# MINI_ESC_V1_0.net
KiCad netlist of a schematic drawn in Altium Designer
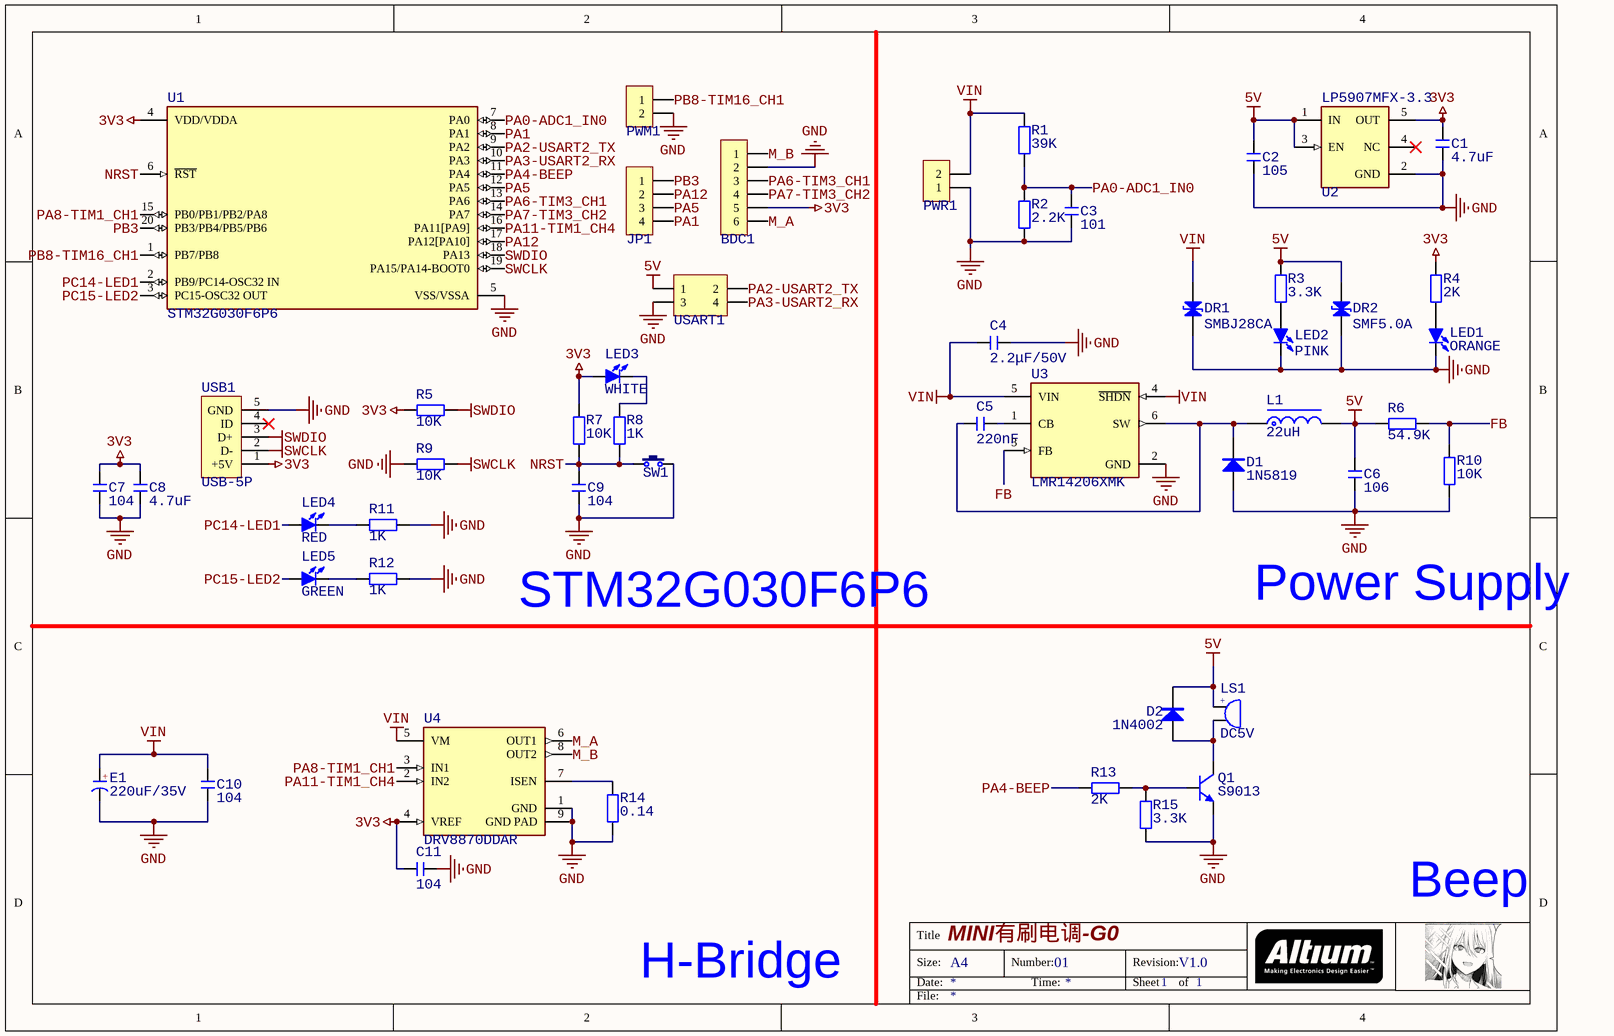
[diagram p0: MINI_ESC_V1.0.SchDoc]

(export (version "E")
  (design (tool "Eeschema 10.0.6"))
  (components
    (comp (ref "BDC1")
      (value "HDR-1X6")
      (footprint "XH2.54-LS-6P")
      (description "6P接插件")
      (libsource (lib "4.6   - 接插件-脚距2.54") (part "Header 6"))
    )
    (comp (ref "C1")
      (value "4.7uF")
      (footprint "C 0603_L")
      (description "无极性贴片电容")
      (libsource (lib "3.1   - 电阻-电容-电感") (part "C"))
    )
    (comp (ref "C2")
      (value "105")
      (footprint "C 0603_L")
      (description "无极性贴片电容")
      (libsource (lib "3.1   - 电阻-电容-电感") (part "C"))
    )
    (comp (ref "C3")
      (value "101")
      (footprint "C 0603_L")
      (description "无极性贴片电容")
      (libsource (lib "3.1   - 电阻-电容-电感") (part "C"))
    )
    (comp (ref "C4")
      (value "2.2μF/50V")
      (footprint "C 0603_L")
      (description "无极性贴片电容")
      (libsource (lib "3.1   - 电阻-电容-电感") (part "C"))
    )
    (comp (ref "C5")
      (value "220nF")
      (footprint "C 0603_L")
      (description "无极性贴片电容")
      (libsource (lib "3.1   - 电阻-电容-电感") (part "C"))
    )
    (comp (ref "C6")
      (value "106")
      (footprint "C 0603_L")
      (description "无极性贴片电容")
      (libsource (lib "3.1   - 电阻-电容-电感") (part "C"))
    )
    (comp (ref "C7")
      (value "104")
      (footprint "C 0402_L")
      (description "无极性贴片电容")
      (libsource (lib "3.1   - 电阻-电容-电感") (part "C"))
    )
    (comp (ref "C8")
      (value "4.7uF")
      (footprint "C 0402_L")
      (description "无极性贴片电容")
      (libsource (lib "3.1   - 电阻-电容-电感") (part "C"))
    )
    (comp (ref "C9")
      (value "104")
      (footprint "C 0603_L")
      (description "无极性贴片电容")
      (libsource (lib "3.1   - 电阻-电容-电感") (part "C"))
    )
    (comp (ref "C10")
      (value "104")
      (footprint "C 0402_L")
      (description "无极性贴片电容")
      (libsource (lib "3.1   - 电阻-电容-电感") (part "C"))
    )
    (comp (ref "C11")
      (value "104")
      (footprint "C 0402_L")
      (description "无极性贴片电容")
      (libsource (lib "3.1   - 电阻-电容-电感") (part "C"))
    )
    (comp (ref "D1")
      (value "1N5819")
      (footprint "SOD-123")
      (description "肖特基二极管")
      (libsource (lib "8.1   - 二极管-整流桥") (part "1N5819"))
    )
    (comp (ref "D2")
      (value "1N4002")
      (footprint "SOD-123")
      (description "整流二极管")
      (libsource (lib "8.1   - 二极管-整流桥") (part "1N4007"))
    )
    (comp (ref "DR1")
      (value "SMBJ28CA")
      (footprint "Diode:SMB")
      (description "瞬态电压抑制二极管")
      (libsource (lib "8.1   - 二极管-整流桥") (part "DR"))
    )
    (comp (ref "DR2")
      (value "SMF5.0A")
      (footprint "SOD-323")
      (description "瞬态电压抑制二极管")
      (libsource (lib "8.1   - 二极管-整流桥") (part "DR"))
    )
    (comp (ref "E1")
      (value "220uF/35V")
      (footprint "CAP 3.5*8*11.5-H - BK")
      (description "直插电解电容")
      (libsource (lib "3.1   - 电阻-电容-电感") (part "C-CAP"))
    )
    (comp (ref "JP1")
      (value "HDR-1X4")
      (footprint "HDR2.54-LI-4P")
      (description "4P接插件")
      (libsource (lib "4.6   - 接插件-脚距2.54") (part "Header 4"))
    )
    (comp (ref "L1")
      (value "22uH")
      (footprint "NR4030")
      (description "NR磁胶电感")
      (libsource (lib "3.1   - 电阻-电容-电感") (part "L-NR"))
    )
    (comp (ref "LED1")
      (value "ORANGE")
      (footprint "LED 0603R")
      (description "贴片LED")
      (libsource (lib "9.1   - LED") (part "LED-SMD"))
    )
    (comp (ref "LED2")
      (value "PINK")
      (footprint "LED 0603R")
      (description "贴片LED")
      (libsource (lib "9.1   - LED") (part "LED-SMD"))
    )
    (comp (ref "LED3")
      (value "WHITE")
      (footprint "LED 0603W")
      (description "贴片LED")
      (libsource (lib "9.1   - LED") (part "LED-SMD"))
    )
    (comp (ref "LED4")
      (value "RED")
      (footprint "LED 0603R")
      (description "贴片LED")
      (libsource (lib "9.1   - LED") (part "LED-SMD"))
    )
    (comp (ref "LED5")
      (value "GREEN")
      (footprint "LED 0603G")
      (description "贴片LED")
      (libsource (lib "9.1   - LED") (part "LED-SMD"))
    )
    (comp (ref "LS1")
      (value "DC5V")
      (footprint "BEEP 6.5x12x6")
      (description "蜂鸣器")
      (libsource (lib "15.1 - 未分类器件") (part "BEEP"))
    )
    (comp (ref "PWM1")
      (value "HDR-1X2")
      (footprint "GH1.25-LS-2P")
      (description "2P接插件")
      (libsource (lib "4.2   - 接插件-脚距1.25") (part "Header 2"))
    )
    (comp (ref "PWR1")
      (value "绿头卧式2P")
      (footprint "15EDGVM-02P-3.81mm")
      (description "3.81间距")
      (libsource (lib "Elmo接插件") (part "绿头卧式2P"))
    )
    (comp (ref "Q1")
      (value "S9013")
      (footprint "SOT23-3L")
      (description "低频放大-NPN型")
      (libsource (lib "6.2   - 三极管") (part "9013-SMD"))
    )
    (comp (ref "R1")
      (value "39K")
      (footprint "R 0603_L")
      (description "贴片电阻")
      (libsource (lib "3.1   - 电阻-电容-电感") (part "R"))
    )
    (comp (ref "R2")
      (value "2.2K")
      (footprint "R 0603_L")
      (description "贴片电阻")
      (libsource (lib "3.1   - 电阻-电容-电感") (part "R"))
    )
    (comp (ref "R3")
      (value "3.3K")
      (footprint "R 0603_L")
      (description "贴片电阻")
      (libsource (lib "3.1   - 电阻-电容-电感") (part "R"))
    )
    (comp (ref "R4")
      (value "2K")
      (footprint "R 0603_L")
      (description "贴片电阻")
      (libsource (lib "3.1   - 电阻-电容-电感") (part "R"))
    )
    (comp (ref "R5")
      (value "10K")
      (footprint "R 0603_L")
      (description "贴片电阻")
      (libsource (lib "3.1   - 电阻-电容-电感") (part "R"))
    )
    (comp (ref "R6")
      (value "54.9K")
      (footprint "R 0603_L")
      (description "贴片电阻")
      (libsource (lib "3.1   - 电阻-电容-电感") (part "R"))
    )
    (comp (ref "R7")
      (value "10K")
      (footprint "R 0603_L")
      (description "贴片电阻")
      (libsource (lib "3.1   - 电阻-电容-电感") (part "R"))
    )
    (comp (ref "R8")
      (value "1K")
      (footprint "R 0603_L")
      (description "贴片电阻")
      (libsource (lib "3.1   - 电阻-电容-电感") (part "R"))
    )
    (comp (ref "R9")
      (value "10K")
      (footprint "R 0603_L")
      (description "贴片电阻")
      (libsource (lib "3.1   - 电阻-电容-电感") (part "R"))
    )
    (comp (ref "R10")
      (value "10K")
      (footprint "R 0603_L")
      (description "贴片电阻")
      (libsource (lib "3.1   - 电阻-电容-电感") (part "R"))
    )
    (comp (ref "R11")
      (value "1K")
      (footprint "R 0402_L")
      (description "贴片电阻")
      (libsource (lib "3.1   - 电阻-电容-电感") (part "R"))
    )
    (comp (ref "R12")
      (value "1K")
      (footprint "R 0402_L")
      (description "贴片电阻")
      (libsource (lib "3.1   - 电阻-电容-电感") (part "R"))
    )
    (comp (ref "R13")
      (value "2K")
      (footprint "R 0603_L")
      (description "贴片电阻")
      (libsource (lib "3.1   - 电阻-电容-电感") (part "R"))
    )
    (comp (ref "R14")
      (value "0.14")
      (footprint "R 1206_L")
      (description "贴片电阻")
      (libsource (lib "3.1   - 电阻-电容-电感") (part "R"))
    )
    (comp (ref "R15")
      (value "3.3K")
      (footprint "R 0603_L")
      (description "贴片电阻")
      (libsource (lib "3.1   - 电阻-电容-电感") (part "R"))
    )
    (comp (ref "SW1")
      (value "6x6x5")
      (footprint "TS 2PIN 6x6x4.8")
      (description "2脚贴片6x6无声硅胶轻触开关")
      (libsource (lib "KEY") (part "TSW SMD-2Pin-6x6"))
    )
    (comp (ref "U1")
      (value "STM32G030F6P6")
      (footprint "STMicroelectronics_TSSOP20-YA_IPC_C")
      (libsource (lib "高级IC") (part "STM32G030F6P6"))
    )
    (comp (ref "U2")
      (value "LP5907MFX-3.3")
      (footprint "Diodes_SOT25_MFG")
      (description "250-mA ultra-low-noise low-IQ low-dropout (LDO) linear regulator 5-SOT-23 -40 to 125")
      (libsource (lib "高级IC") (part "LP5907MFX-3.3-NOPB"))
    )
    (comp (ref "U3")
      (value "LMR14206XMK")
      (footprint "Texas_Instruments_DDC0006A_0")
      (description "4.5V to 42V, 0.6A Step-Down DC/DC Switching Regulator in SOT-23 Package 6-SOT-23-THIN -40 to 125")
      (libsource (lib "高级IC") (part "LMR14206XMK"))
    )
    (comp (ref "U4")
      (value "DRV8870DDAR")
      (footprint "Texas_Instruments_DDA0008J_IPC_C")
      (description "50-V, 3.6-A H-bridge motor driver with current regulation 8-SO PowerPAD -40 to 125")
      (libsource (lib "高级IC") (part "DRV8870DDAR"))
    )
    (comp (ref "USART1")
      (value "Header2X2")
      (footprint "HDR2.54-M-LS-2x2P")
      (description "2*2P接插件")
      (libsource (lib "4.6   - 接插件-脚距2.54") (part "Header 2X2"))
    )
    (comp (ref "USB1")
      (value "USB-5P")
      (footprint "USB-MICRO_E")
      (description "微型USB母座")
      (libsource (lib "4.1   - 接口类") (part "USB-5P"))
    )
  )
  (nets
    (net (code "1") (name "/FB") (class "Default")
      (node (ref "R10") (pin "1") (pinfunction "1_1") (pintype "passive"))
      (node (ref "R6") (pin "2") (pinfunction "2_2") (pintype "passive"))
      (node (ref "U3") (pin "3") (pinfunction "FB_3") (pintype "input"))
    )
    (net (code "2") (name "/M_A") (class "Default")
      (node (ref "BDC1") (pin "6") (pinfunction "6_6") (pintype "passive"))
      (node (ref "U4") (pin "6") (pinfunction "OUT1_6") (pintype "output"))
    )
    (net (code "3") (name "/M_B") (class "Default")
      (node (ref "BDC1") (pin "1") (pinfunction "1_1") (pintype "passive"))
      (node (ref "U4") (pin "8") (pinfunction "OUT2_8") (pintype "output"))
    )
    (net (code "4") (name "/NRST") (class "Default")
      (node (ref "C9") (pin "2") (pinfunction "2_2") (pintype "passive"))
      (node (ref "R7") (pin "1") (pinfunction "1_1") (pintype "passive"))
      (node (ref "R8") (pin "1") (pinfunction "1_1") (pintype "passive"))
      (node (ref "SW1") (pin "1") (pinfunction "1_1") (pintype "passive"))
      (node (ref "U1") (pin "6") (pinfunction "~{RST}_6") (pintype "input"))
    )
    (net (code "5") (name "/PA0-ADC1_IN0") (class "Default")
      (node (ref "C3") (pin "2") (pinfunction "2_2") (pintype "passive"))
      (node (ref "R1") (pin "1") (pinfunction "1_1") (pintype "passive"))
      (node (ref "R2") (pin "2") (pinfunction "2_2") (pintype "passive"))
      (node (ref "U1") (pin "7") (pinfunction "PA0_7") (pintype "bidirectional"))
    )
    (net (code "6") (name "/PA1") (class "Default")
      (node (ref "JP1") (pin "4") (pinfunction "4_4") (pintype "passive"))
      (node (ref "U1") (pin "8") (pinfunction "PA1_8") (pintype "bidirectional"))
    )
    (net (code "7") (name "/PA2-USART2_TX") (class "Default")
      (node (ref "U1") (pin "9") (pinfunction "PA2_9") (pintype "bidirectional"))
      (node (ref "USART1") (pin "2") (pinfunction "2_2") (pintype "passive"))
    )
    (net (code "8") (name "/PA3-USART2_RX") (class "Default")
      (node (ref "U1") (pin "10") (pinfunction "PA3_10") (pintype "bidirectional"))
      (node (ref "USART1") (pin "4") (pinfunction "4_4") (pintype "passive"))
    )
    (net (code "9") (name "/PA4-BEEP") (class "Default")
      (node (ref "R13") (pin "1") (pinfunction "1_1") (pintype "passive"))
      (node (ref "U1") (pin "11") (pinfunction "PA4_11") (pintype "bidirectional"))
    )
    (net (code "10") (name "/PA5") (class "Default")
      (node (ref "JP1") (pin "3") (pinfunction "3_3") (pintype "passive"))
      (node (ref "U1") (pin "12") (pinfunction "PA5_12") (pintype "bidirectional"))
    )
    (net (code "11") (name "/PA6-TIM3_CH1") (class "Default")
      (node (ref "BDC1") (pin "3") (pinfunction "3_3") (pintype "passive"))
      (node (ref "U1") (pin "13") (pinfunction "PA6_13") (pintype "bidirectional"))
    )
    (net (code "12") (name "/PA7-TIM3_CH2") (class "Default")
      (node (ref "BDC1") (pin "4") (pinfunction "4_4") (pintype "passive"))
      (node (ref "U1") (pin "14") (pinfunction "PA7_14") (pintype "bidirectional"))
    )
    (net (code "13") (name "/PA8-TIM1_CH1") (class "Default")
      (node (ref "U1") (pin "15") (pinfunction "PB0/PB1/PB2/PA8_15") (pintype "bidirectional"))
      (node (ref "U4") (pin "3") (pinfunction "IN1_3") (pintype "input"))
    )
    (net (code "14") (name "/PA11-TIM1_CH4") (class "Default")
      (node (ref "U1") (pin "16") (pinfunction "PA11[PA9]_16") (pintype "bidirectional"))
      (node (ref "U4") (pin "2") (pinfunction "IN2_2") (pintype "input"))
    )
    (net (code "15") (name "/PA12") (class "Default")
      (node (ref "JP1") (pin "2") (pinfunction "2_2") (pintype "passive"))
      (node (ref "U1") (pin "17") (pinfunction "PA12[PA10]_17") (pintype "bidirectional"))
    )
    (net (code "16") (name "/PB3") (class "Default")
      (node (ref "JP1") (pin "1") (pinfunction "1_1") (pintype "passive"))
      (node (ref "U1") (pin "20") (pinfunction "PB3/PB4/PB5/PB6_20") (pintype "bidirectional"))
    )
    (net (code "17") (name "/PB8-TIM16_CH1") (class "Default")
      (node (ref "PWM1") (pin "1") (pinfunction "1_1") (pintype "passive"))
      (node (ref "U1") (pin "1") (pinfunction "PB7/PB8_1") (pintype "bidirectional"))
    )
    (net (code "18") (name "/PC14-LED1") (class "Default")
      (node (ref "LED4") (pin "1") (pinfunction "A_1") (pintype "passive"))
      (node (ref "U1") (pin "2") (pinfunction "PB9/PC14-OSC32_IN_2") (pintype "bidirectional"))
    )
    (net (code "19") (name "/PC15-LED2") (class "Default")
      (node (ref "LED5") (pin "1") (pinfunction "A_1") (pintype "passive"))
      (node (ref "U1") (pin "3") (pinfunction "PC15-OSC32_OUT_3") (pintype "bidirectional"))
    )
    (net (code "20") (name "3V3") (class "Default")
      (node (ref "BDC1") (pin "5") (pinfunction "5_5") (pintype "passive"))
      (node (ref "C1") (pin "2") (pinfunction "2_2") (pintype "passive"))
      (node (ref "C11") (pin "2") (pinfunction "2_2") (pintype "passive"))
      (node (ref "C7") (pin "2") (pinfunction "2_2") (pintype "passive"))
      (node (ref "C8") (pin "2") (pinfunction "2_2") (pintype "passive"))
      (node (ref "LED3") (pin "1") (pinfunction "A_1") (pintype "passive"))
      (node (ref "R4") (pin "2") (pinfunction "2_2") (pintype "passive"))
      (node (ref "R5") (pin "2") (pinfunction "2_2") (pintype "passive"))
      (node (ref "R7") (pin "2") (pinfunction "2_2") (pintype "passive"))
      (node (ref "U1") (pin "4") (pinfunction "VDD/VDDA_4") (pintype "power_in"))
      (node (ref "U2") (pin "5") (pinfunction "OUT_5") (pintype "power_in"))
      (node (ref "U4") (pin "4") (pinfunction "VREF_4") (pintype "input"))
      (node (ref "USB1") (pin "1") (pinfunction "+5V_1") (pintype "passive"))
    )
    (net (code "21") (name "5V") (class "Default")
      (node (ref "C2") (pin "2") (pinfunction "2_2") (pintype "passive"))
      (node (ref "C6") (pin "1") (pinfunction "1_1") (pintype "passive"))
      (node (ref "D2") (pin "2") (pinfunction "K_2") (pintype "passive"))
      (node (ref "DR2") (pin "2") (pinfunction "K_2") (pintype "passive"))
      (node (ref "L1") (pin "2") (pinfunction "2_2") (pintype "passive"))
      (node (ref "LS1") (pin "1") (pinfunction "1_1") (pintype "passive"))
      (node (ref "R3") (pin "2") (pinfunction "2_2") (pintype "passive"))
      (node (ref "R6") (pin "1") (pinfunction "1_1") (pintype "passive"))
      (node (ref "U2") (pin "1") (pinfunction "IN_1") (pintype "power_in"))
      (node (ref "U2") (pin "3") (pinfunction "EN_3") (pintype "input"))
      (node (ref "USART1") (pin "1") (pinfunction "1_1") (pintype "passive"))
    )
    (net (code "22") (name "GND") (class "Default")
      (node (ref "BDC1") (pin "2") (pinfunction "2_2") (pintype "passive"))
      (node (ref "C1") (pin "1") (pinfunction "1_1") (pintype "passive"))
      (node (ref "C10") (pin "1") (pinfunction "1_1") (pintype "passive"))
      (node (ref "C11") (pin "1") (pinfunction "1_1") (pintype "passive"))
      (node (ref "C2") (pin "1") (pinfunction "1_1") (pintype "passive"))
      (node (ref "C3") (pin "1") (pinfunction "1_1") (pintype "passive"))
      (node (ref "C4") (pin "2") (pinfunction "2_2") (pintype "passive"))
      (node (ref "C6") (pin "2") (pinfunction "2_2") (pintype "passive"))
      (node (ref "C7") (pin "1") (pinfunction "1_1") (pintype "passive"))
      (node (ref "C8") (pin "1") (pinfunction "1_1") (pintype "passive"))
      (node (ref "C9") (pin "1") (pinfunction "1_1") (pintype "passive"))
      (node (ref "D1") (pin "1") (pinfunction "A_1") (pintype "passive"))
      (node (ref "DR1") (pin "2") (pinfunction "K_2") (pintype "passive"))
      (node (ref "DR2") (pin "1") (pinfunction "A_1") (pintype "passive"))
      (node (ref "E1") (pin "2") (pinfunction "K_2") (pintype "passive"))
      (node (ref "LED1") (pin "2") (pinfunction "K_2") (pintype "passive"))
      (node (ref "LED2") (pin "2") (pinfunction "K_2") (pintype "passive"))
      (node (ref "PWM1") (pin "2") (pinfunction "2_2") (pintype "passive"))
      (node (ref "PWR1") (pin "1") (pinfunction "1_1") (pintype "passive"))
      (node (ref "Q1") (pin "2") (pinfunction "E_2") (pintype "passive"))
      (node (ref "R10") (pin "2") (pinfunction "2_2") (pintype "passive"))
      (node (ref "R11") (pin "1") (pinfunction "1_1") (pintype "passive"))
      (node (ref "R12") (pin "1") (pinfunction "1_1") (pintype "passive"))
      (node (ref "R14") (pin "1") (pinfunction "1_1") (pintype "passive"))
      (node (ref "R15") (pin "1") (pinfunction "1_1") (pintype "passive"))
      (node (ref "R2") (pin "1") (pinfunction "1_1") (pintype "passive"))
      (node (ref "R9") (pin "2") (pinfunction "2_2") (pintype "passive"))
      (node (ref "SW1") (pin "2") (pinfunction "2_2") (pintype "passive"))
      (node (ref "U1") (pin "5") (pinfunction "VSS/VSSA_5") (pintype "power_in"))
      (node (ref "U2") (pin "2") (pinfunction "GND_2") (pintype "power_in"))
      (node (ref "U3") (pin "2") (pinfunction "GND_2") (pintype "power_in"))
      (node (ref "U4") (pin "1") (pinfunction "GND_1") (pintype "power_in"))
      (node (ref "U4") (pin "9") (pinfunction "GND_PAD_9") (pintype "power_in"))
      (node (ref "USART1") (pin "3") (pinfunction "3_3") (pintype "passive"))
      (node (ref "USB1") (pin "5") (pinfunction "GND_5") (pintype "passive"))
    )
    (net (code "23") (name "Net-(D1-K)") (class "Default")
      (node (ref "C5") (pin "2") (pinfunction "2_2") (pintype "passive"))
      (node (ref "D1") (pin "2") (pinfunction "K_2") (pintype "passive"))
      (node (ref "L1") (pin "1") (pinfunction "1_1") (pintype "passive"))
      (node (ref "U3") (pin "6") (pinfunction "SW_6") (pintype "output"))
    )
    (net (code "24") (name "Net-(D2-A)") (class "Default")
      (node (ref "D2") (pin "1") (pinfunction "A_1") (pintype "passive"))
      (node (ref "LS1") (pin "2") (pinfunction "2_2") (pintype "passive"))
      (node (ref "Q1") (pin "3") (pinfunction "C_3") (pintype "passive"))
    )
    (net (code "25") (name "Net-(LED1-A)") (class "Default")
      (node (ref "LED1") (pin "1") (pinfunction "A_1") (pintype "passive"))
      (node (ref "R4") (pin "1") (pinfunction "1_1") (pintype "passive"))
    )
    (net (code "26") (name "Net-(LED2-A)") (class "Default")
      (node (ref "LED2") (pin "1") (pinfunction "A_1") (pintype "passive"))
      (node (ref "R3") (pin "1") (pinfunction "1_1") (pintype "passive"))
    )
    (net (code "27") (name "Net-(LED3-K)") (class "Default")
      (node (ref "LED3") (pin "2") (pinfunction "K_2") (pintype "passive"))
      (node (ref "R8") (pin "2") (pinfunction "2_2") (pintype "passive"))
    )
    (net (code "28") (name "Net-(LED4-K)") (class "Default")
      (node (ref "LED4") (pin "2") (pinfunction "K_2") (pintype "passive"))
      (node (ref "R11") (pin "2") (pinfunction "2_2") (pintype "passive"))
    )
    (net (code "29") (name "Net-(LED5-K)") (class "Default")
      (node (ref "LED5") (pin "2") (pinfunction "K_2") (pintype "passive"))
      (node (ref "R12") (pin "2") (pinfunction "2_2") (pintype "passive"))
    )
    (net (code "30") (name "Net-(Q1-B)") (class "Default")
      (node (ref "Q1") (pin "1") (pinfunction "B_1") (pintype "passive"))
      (node (ref "R13") (pin "2") (pinfunction "2_2") (pintype "passive"))
      (node (ref "R15") (pin "2") (pinfunction "2_2") (pintype "passive"))
    )
    (net (code "31") (name "Net-(U3-CB)") (class "Default")
      (node (ref "C5") (pin "1") (pinfunction "1_1") (pintype "passive"))
      (node (ref "U3") (pin "1") (pinfunction "CB_1") (pintype "passive"))
    )
    (net (code "32") (name "Net-(U4-ISEN)") (class "Default")
      (node (ref "R14") (pin "2") (pinfunction "2_2") (pintype "passive"))
      (node (ref "U4") (pin "7") (pinfunction "ISEN_7") (pintype "passive"))
    )
    (net (code "33") (name "SWCLK") (class "Default")
      (node (ref "R9") (pin "1") (pinfunction "1_1") (pintype "passive"))
      (node (ref "U1") (pin "19") (pinfunction "PA15/PA14-BOOT0_19") (pintype "bidirectional"))
      (node (ref "USB1") (pin "2") (pinfunction "D-_2") (pintype "passive"))
    )
    (net (code "34") (name "SWDIO") (class "Default")
      (node (ref "R5") (pin "1") (pinfunction "1_1") (pintype "passive"))
      (node (ref "U1") (pin "18") (pinfunction "PA13_18") (pintype "bidirectional"))
      (node (ref "USB1") (pin "3") (pinfunction "D+_3") (pintype "passive"))
    )
    (net (code "35") (name "VIN") (class "Default")
      (node (ref "C10") (pin "2") (pinfunction "2_2") (pintype "passive"))
      (node (ref "C4") (pin "1") (pinfunction "1_1") (pintype "passive"))
      (node (ref "DR1") (pin "1") (pinfunction "A_1") (pintype "passive"))
      (node (ref "E1") (pin "1") (pinfunction "A_1") (pintype "passive"))
      (node (ref "PWR1") (pin "2") (pinfunction "2_2") (pintype "passive"))
      (node (ref "R1") (pin "2") (pinfunction "2_2") (pintype "passive"))
      (node (ref "U3") (pin "4") (pinfunction "~{SHDN}_4") (pintype "input"))
      (node (ref "U3") (pin "5") (pinfunction "VIN_5") (pintype "power_in"))
      (node (ref "U4") (pin "5") (pinfunction "VM_5") (pintype "power_in"))
    )
    (net (code "36") (name "unconnected-(U2-NC-Pad4)") (class "Default")
      (node (ref "U2") (pin "4") (pinfunction "NC_4") (pintype "passive+no_connect"))
    )
    (net (code "37") (name "unconnected-(USB1-ID-Pad4)") (class "Default")
      (node (ref "USB1") (pin "4") (pinfunction "ID_4") (pintype "passive+no_connect"))
    )
  )
)
